# AD9156.net
KiCad netlist of a schematic drawn in Altium Designer
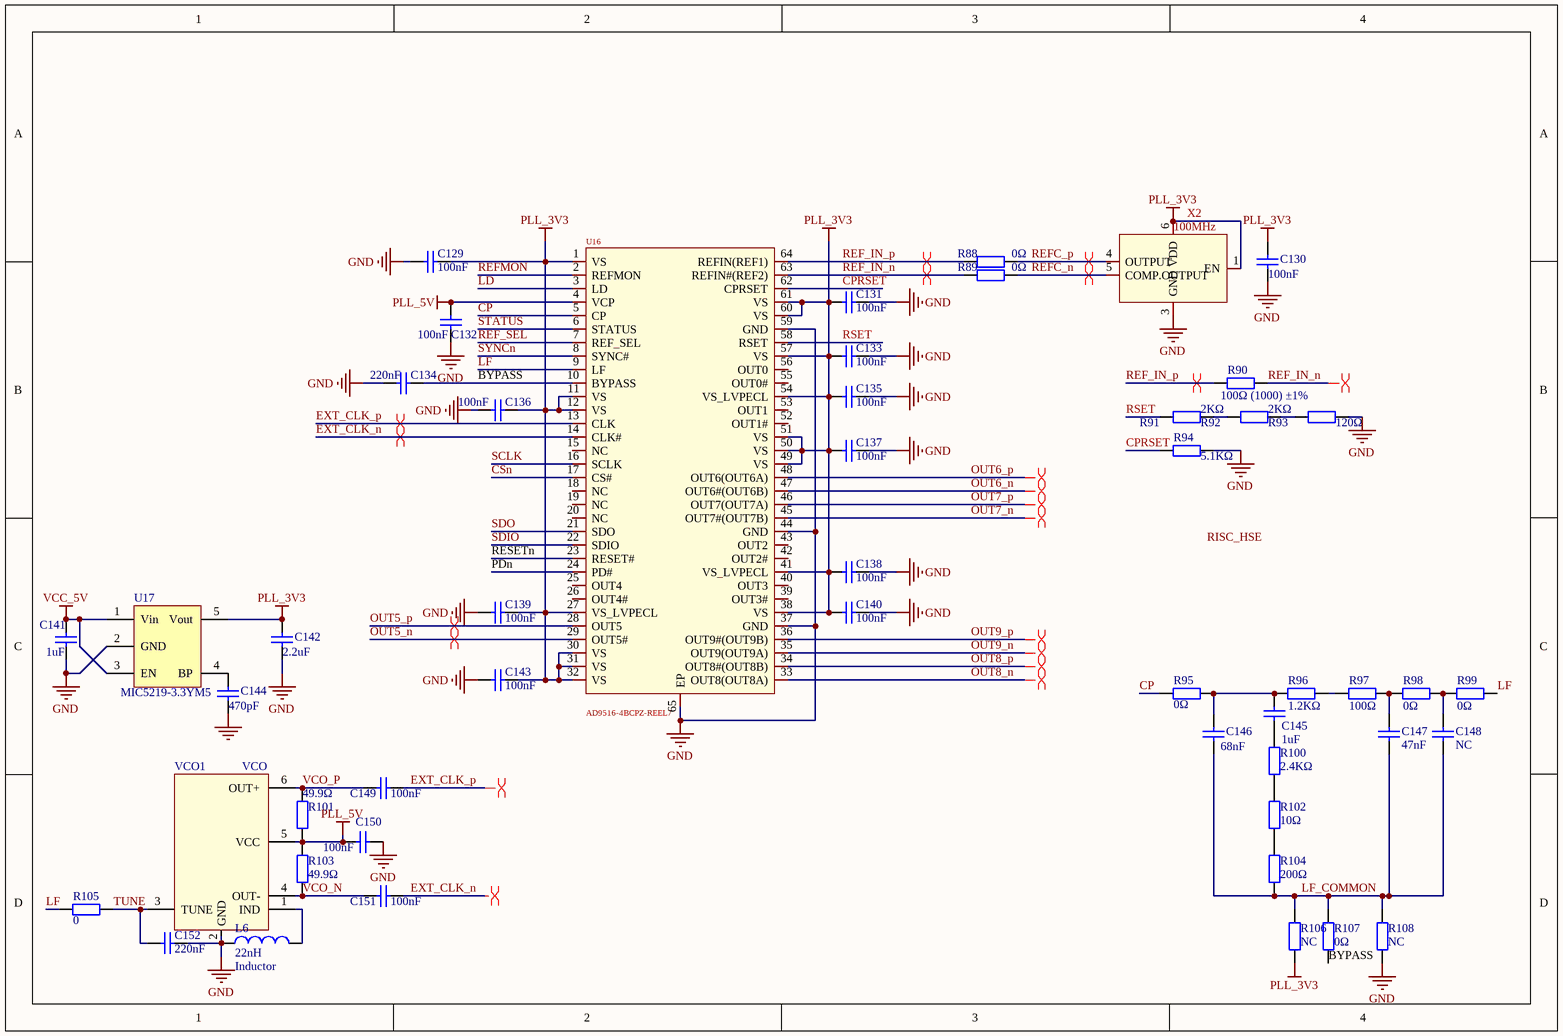
[diagram p0: AD9156.SchDoc]

(export (version "E")
  (design (tool "Eeschema 10.0.6"))
  (components
    (comp (ref "C129")
      (value "100nF")
      (footprint "0201")
      (description "贴片电容")
      (libsource (lib "Miscellaneous Devices LC") (part "0402 100nF (104) 10% 16V"))
    )
    (comp (ref "C130")
      (value "100nF")
      (footprint "0201")
      (description "贴片电容")
      (libsource (lib "Miscellaneous Devices LC") (part "0402 100nF (104) 10% 16V"))
    )
    (comp (ref "C131")
      (value "100nF")
      (footprint "0201")
      (description "贴片电容")
      (libsource (lib "Miscellaneous Devices LC") (part "0402 100nF (104) 10% 16V"))
    )
    (comp (ref "C132")
      (value "100nF")
      (footprint "0201")
      (description "贴片电容")
      (libsource (lib "Miscellaneous Devices LC") (part "0402 100nF (104) 10% 16V"))
    )
    (comp (ref "C133")
      (value "100nF")
      (footprint "0201")
      (description "贴片电容")
      (libsource (lib "Miscellaneous Devices LC") (part "0402 100nF (104) 10% 16V"))
    )
    (comp (ref "C134")
      (value "220nF")
      (footprint "0805_C")
      (description "贴片电容")
      (libsource (lib "Miscellaneous Devices LC") (part "0402 220nF (224) 10% 16V"))
    )
    (comp (ref "C135")
      (value "100nF")
      (footprint "0201")
      (description "贴片电容")
      (libsource (lib "Miscellaneous Devices LC") (part "0402 100nF (104) 10% 16V"))
    )
    (comp (ref "C136")
      (value "100nF")
      (footprint "0201")
      (description "贴片电容")
      (libsource (lib "Miscellaneous Devices LC") (part "0402 100nF (104) 10% 16V"))
    )
    (comp (ref "C137")
      (value "100nF")
      (footprint "0201")
      (description "贴片电容")
      (libsource (lib "Miscellaneous Devices LC") (part "0402 100nF (104) 10% 16V"))
    )
    (comp (ref "C138")
      (value "100nF")
      (footprint "0201")
      (description "贴片电容")
      (libsource (lib "Miscellaneous Devices LC") (part "0402 100nF (104) 10% 16V"))
    )
    (comp (ref "C139")
      (value "100nF")
      (footprint "0201")
      (description "贴片电容")
      (libsource (lib "Miscellaneous Devices LC") (part "0402 100nF (104) 10% 16V"))
    )
    (comp (ref "C140")
      (value "100nF")
      (footprint "0201")
      (description "贴片电容")
      (libsource (lib "Miscellaneous Devices LC") (part "0402 100nF (104) 10% 16V"))
    )
    (comp (ref "C141")
      (value "1uF")
      (footprint "0805_C")
      (description "贴片电容")
      (libsource (lib "Miscellaneous Devices LC") (part "0805 1uF (105) 10% 50V"))
    )
    (comp (ref "C142")
      (value "2.2uF")
      (footprint "0805_C")
      (description "贴片电容")
      (libsource (lib "Miscellaneous Devices LC") (part "0805 1uF (105) 10% 50V"))
    )
    (comp (ref "C143")
      (value "100nF")
      (footprint "0201")
      (description "贴片电容")
      (libsource (lib "Miscellaneous Devices LC") (part "0402 100nF (104) 10% 16V"))
    )
    (comp (ref "C144")
      (value "470pF")
      (footprint "0805_C")
      (description "贴片电容")
      (libsource (lib "Miscellaneous Devices LC") (part "0805 1uF (105) 10% 50V"))
    )
    (comp (ref "C145")
      (value "1uF")
      (footprint "0805_C")
      (description "贴片电容")
      (libsource (lib "Miscellaneous Devices LC") (part "0805 47nF (473) 10% 50V"))
    )
    (comp (ref "C146")
      (value "68nF")
      (footprint "0805_C")
      (description "贴片电容")
      (libsource (lib "Miscellaneous Devices LC") (part "0603 68nF (683) 10% 50V"))
    )
    (comp (ref "C147")
      (value "47nF")
      (footprint "0805_C")
      (description "贴片电容")
      (libsource (lib "Miscellaneous Devices LC") (part "0805 47nF (473) 10% 50V"))
    )
    (comp (ref "C148")
      (value "NC")
      (footprint "0805_C")
      (description "贴片电容")
      (libsource (lib "Miscellaneous Devices LC") (part "0805 47nF (473) 10% 50V"))
    )
    (comp (ref "C149")
      (value "100nF")
      (footprint "0805_C")
      (description "贴片电容")
      (libsource (lib "Miscellaneous Devices LC") (part "0805 100nF(104) 10% 50V"))
    )
    (comp (ref "C150")
      (value "100nF")
      (footprint "0805_C")
      (description "贴片电容")
      (libsource (lib "Miscellaneous Devices LC") (part "0805 100nF(104) 10% 50V"))
    )
    (comp (ref "C151")
      (value "100nF")
      (footprint "0805_C")
      (description "贴片电容")
      (libsource (lib "Miscellaneous Devices LC") (part "0805 100nF(104) 10% 50V"))
    )
    (comp (ref "C152")
      (value "220nF")
      (footprint "0805_C")
      (description "贴片电容")
      (libsource (lib "Miscellaneous Devices LC") (part "0805 100nF(104) 10% 50V"))
    )
    (comp (ref "L6")
      (value "Inductor")
      (footprint "0805_L")
      (fields (field (name "ALTIUM_VALUE") "22nH") (field (name "PUBLISHER") "Altium Limited"))
      (libsource (lib "Miscellaneous Devices") (part "Inductor"))
    )
    (comp (ref "R88")
      (value "0Ω")
      (footprint "0805_R")
      (description "贴片电阻")
      (libsource (lib "Miscellaneous Devices LC") (part "0402 0Ω (0R0) 1%"))
    )
    (comp (ref "R89")
      (value "0Ω")
      (footprint "0805_R")
      (description "贴片电阻")
      (libsource (lib "Miscellaneous Devices LC") (part "0402 0Ω (0R0) 1%"))
    )
    (comp (ref "R90")
      (value "100Ω (1000) ±1%")
      (footprint "0805_R")
      (description "贴片电阻")
      (libsource (lib "Miscellaneous Devices LC") (part "0402 100Ω (1000) 1%"))
    )
    (comp (ref "R91")
      (value "2KΩ")
      (footprint "0805_R")
      (description "贴片电阻")
      (libsource (lib "Miscellaneous Devices LC") (part "0402 2KΩ (2001) 1%"))
    )
    (comp (ref "R92")
      (value "2KΩ")
      (footprint "0805_R")
      (description "贴片电阻")
      (libsource (lib "Miscellaneous Devices LC") (part "0402 2KΩ (2001) 1%"))
    )
    (comp (ref "R93")
      (value "120Ω")
      (footprint "0805_R")
      (description "贴片电阻")
      (libsource (lib "Miscellaneous Devices LC") (part "0402 120KΩ (1203) 1%"))
    )
    (comp (ref "R94")
      (value "5.1KΩ")
      (footprint "0805_R")
      (description "贴片电阻")
      (libsource (lib "Miscellaneous Devices LC") (part "0402 5.1KΩ (5101) 1%"))
    )
    (comp (ref "R95")
      (value "0Ω")
      (footprint "0805_R")
      (description "贴片电阻")
      (libsource (lib "") (part "0805 0Ω (0R0) 1%_1"))
    )
    (comp (ref "R96")
      (value "1.2KΩ")
      (footprint "0805_R")
      (description "贴片电阻")
      (libsource (lib "") (part "0805 0Ω (0R0) 1%_1"))
    )
    (comp (ref "R97")
      (value "100Ω")
      (footprint "0805_R")
      (description "贴片电阻")
      (libsource (lib "") (part "0805 0Ω (0R0) 1%_1"))
    )
    (comp (ref "R98")
      (value "0Ω")
      (footprint "0805_R")
      (description "贴片电阻")
      (libsource (lib "") (part "0805 0Ω (0R0) 1%_1"))
    )
    (comp (ref "R99")
      (value "0Ω")
      (footprint "0805_R")
      (description "贴片电阻")
      (libsource (lib "") (part "0805 0Ω (0R0) 1%_1"))
    )
    (comp (ref "R100")
      (value "2.4KΩ")
      (footprint "0805_R")
      (description "贴片电阻")
      (libsource (lib "Miscellaneous Devices LC") (part "0805 0Ω (0R0) 1%"))
    )
    (comp (ref "R101")
      (value "49.9Ω")
      (footprint "0805_R")
      (description "贴片电阻")
      (libsource (lib "Miscellaneous Devices LC") (part "0805 49.9Ω (49R9) 1%"))
    )
    (comp (ref "R102")
      (value "10Ω")
      (footprint "0805_R")
      (description "贴片电阻")
      (libsource (lib "Miscellaneous Devices LC") (part "0805 0Ω (0R0) 1%"))
    )
    (comp (ref "R103")
      (value "49.9Ω")
      (footprint "0805_R")
      (description "贴片电阻")
      (libsource (lib "Miscellaneous Devices LC") (part "0805 49.9Ω (49R9) 1%"))
    )
    (comp (ref "R104")
      (value "200Ω")
      (footprint "0805_R")
      (description "贴片电阻")
      (libsource (lib "Miscellaneous Devices LC") (part "0805 0Ω (0R0) 1%"))
    )
    (comp (ref "R105")
      (value "0")
      (footprint "0805_R")
      (description "贴片电阻")
      (libsource (lib "") (part "0805 49.9Ω (49R9) 1%_1"))
    )
    (comp (ref "R106")
      (value "NC")
      (footprint "0805_R")
      (description "贴片电阻")
      (libsource (lib "Miscellaneous Devices LC") (part "0805 0Ω (0R0) 1%"))
    )
    (comp (ref "R107")
      (value "0Ω")
      (footprint "0805_R")
      (description "贴片电阻")
      (libsource (lib "Miscellaneous Devices LC") (part "0805 0Ω (0R0) 1%"))
    )
    (comp (ref "R108")
      (value "NC")
      (footprint "0805_R")
      (description "贴片电阻")
      (libsource (lib "Miscellaneous Devices LC") (part "0805 0Ω (0R0) 1%"))
    )
    (comp (ref "U16")
      (value "AD9516-4BCPZ-REEL7")
      (footprint "LFCSP-64_L9.0-W8.8-P0.50-TL-EP6.2")
      (description "时钟分配芯片")
      (fields (field (name "MANUFACTURER") "ADI(亚德诺)"))
      (libsource (lib "yy_tech") (part "AD9516-4BCPZ-REEL7"))
    )
    (comp (ref "U17")
      (value "MIC5219-3.3YM5")
      (footprint "SOT-23-5")
      (description "3.3v低压差稳压芯片")
      (libsource (lib "五向开关") (part "RT9193-33"))
    )
    (comp (ref "VCO1")
      (value "VCO")
      (footprint "SOT-23-6_L2.9-W1.6-P0.95-LS2.8-BL")
      (description "300MHz~500MHz VCO")
      (libsource (lib "五向开关") (part "MAX2608"))
    )
    (comp (ref "X2")
      (value "100MHz")
      (footprint "OSC-SMD_6P-L3.2-W2.5-BL_SG3225EAN")
      (description "3225有源差分晶体")
      (fields
        (field (name "MANUFACTURER") "SCTF(星通时频)")
        (field (name "MANUFACTURER PART") "SX3DF100.000B20F30PNN")
      )
      (libsource (lib "五向开关") (part "SX3DF100.000B20F30PNN"))
    )
  )
  (nets
    (net (code "1") (name "/BYPASS") (class "Default")
      (node (ref "C134") (pin "2") (pinfunction "2_2") (pintype "passive"))
      (node (ref "R107") (pin "1") (pinfunction "1_1") (pintype "passive"))
      (node (ref "U16") (pin "10") (pinfunction "BYPASS_10") (pintype "passive"))
    )
    (net (code "2") (name "/CP") (class "Default")
      (node (ref "R95") (pin "1") (pinfunction "1_1") (pintype "passive"))
      (node (ref "U16") (pin "5") (pinfunction "CP_5") (pintype "passive"))
    )
    (net (code "3") (name "/CPRSET") (class "Default")
      (node (ref "R94") (pin "1") (pinfunction "1_1") (pintype "passive"))
      (node (ref "U16") (pin "62") (pinfunction "CPRSET_62") (pintype "passive"))
    )
    (net (code "4") (name "/CSn") (class "Default")
      (node (ref "U16") (pin "17") (pinfunction "CS#_17") (pintype "passive"))
    )
    (net (code "5") (name "/EXT_CLK_n") (class "Default")
      (node (ref "C151") (pin "1") (pinfunction "1_1") (pintype "passive"))
      (node (ref "U16") (pin "14") (pinfunction "CLK#_14") (pintype "passive"))
    )
    (net (code "6") (name "/EXT_CLK_p") (class "Default")
      (node (ref "C149") (pin "1") (pinfunction "1_1") (pintype "passive"))
      (node (ref "U16") (pin "13") (pinfunction "CLK_13") (pintype "passive"))
    )
    (net (code "7") (name "/LD") (class "Default")
      (node (ref "U16") (pin "3") (pinfunction "LD_3") (pintype "passive"))
    )
    (net (code "8") (name "/LF") (class "Default")
      (node (ref "R105") (pin "2") (pinfunction "2_2") (pintype "passive"))
      (node (ref "R99") (pin "2") (pinfunction "2_2") (pintype "passive"))
      (node (ref "U16") (pin "9") (pinfunction "LF_9") (pintype "passive"))
    )
    (net (code "9") (name "/LF_COMMON") (class "Default")
      (node (ref "C146") (pin "1") (pinfunction "1_1") (pintype "passive"))
      (node (ref "C147") (pin "1") (pinfunction "1_1") (pintype "passive"))
      (node (ref "C148") (pin "1") (pinfunction "1_1") (pintype "passive"))
      (node (ref "R104") (pin "1") (pinfunction "1_1") (pintype "passive"))
      (node (ref "R106") (pin "2") (pinfunction "2_2") (pintype "passive"))
      (node (ref "R107") (pin "2") (pinfunction "2_2") (pintype "passive"))
      (node (ref "R108") (pin "2") (pinfunction "2_2") (pintype "passive"))
    )
    (net (code "10") (name "/OUT5_n") (class "Default")
      (node (ref "U16") (pin "29") (pinfunction "OUT5#_29") (pintype "passive"))
    )
    (net (code "11") (name "/OUT5_p") (class "Default")
      (node (ref "U16") (pin "28") (pinfunction "OUT5_28") (pintype "passive"))
    )
    (net (code "12") (name "/OUT6_n") (class "Default")
      (node (ref "U16") (pin "47") (pinfunction "OUT6#(OUT6B)_47") (pintype "passive"))
    )
    (net (code "13") (name "/OUT6_p") (class "Default")
      (node (ref "U16") (pin "48") (pinfunction "OUT6(OUT6A)_48") (pintype "passive"))
    )
    (net (code "14") (name "/OUT7_n") (class "Default")
      (node (ref "U16") (pin "45") (pinfunction "OUT7#(OUT7B)_45") (pintype "passive"))
    )
    (net (code "15") (name "/OUT7_p") (class "Default")
      (node (ref "U16") (pin "46") (pinfunction "OUT7(OUT7A)_46") (pintype "passive"))
    )
    (net (code "16") (name "/OUT8_n") (class "Default")
      (node (ref "U16") (pin "33") (pinfunction "OUT8(OUT8A)_33") (pintype "passive"))
    )
    (net (code "17") (name "/OUT8_p") (class "Default")
      (node (ref "U16") (pin "34") (pinfunction "OUT8#(OUT8B)_34") (pintype "passive"))
    )
    (net (code "18") (name "/OUT9_n") (class "Default")
      (node (ref "U16") (pin "35") (pinfunction "OUT9(OUT9A)_35") (pintype "passive"))
    )
    (net (code "19") (name "/OUT9_p") (class "Default")
      (node (ref "U16") (pin "36") (pinfunction "OUT9#(OUT9B)_36") (pintype "passive"))
    )
    (net (code "20") (name "/PDn") (class "Default")
      (node (ref "U16") (pin "24") (pinfunction "PD#_24") (pintype "passive"))
    )
    (net (code "21") (name "/REFC_n") (class "Default")
      (node (ref "R89") (pin "2") (pinfunction "2_2") (pintype "passive"))
      (node (ref "X2") (pin "5") (pinfunction "COMP.OUTPUT_5") (pintype "passive"))
    )
    (net (code "22") (name "/REFC_p") (class "Default")
      (node (ref "R88") (pin "2") (pinfunction "2_2") (pintype "passive"))
      (node (ref "X2") (pin "4") (pinfunction "OUTPUT_4") (pintype "passive"))
    )
    (net (code "23") (name "/REFMON") (class "Default")
      (node (ref "U16") (pin "2") (pinfunction "REFMON_2") (pintype "passive"))
    )
    (net (code "24") (name "/REF_IN_n") (class "Default")
      (node (ref "R89") (pin "1") (pinfunction "1_1") (pintype "passive"))
      (node (ref "R90") (pin "1") (pinfunction "1_1") (pintype "passive"))
      (node (ref "U16") (pin "63") (pinfunction "REFIN#(REF2)_63") (pintype "passive"))
    )
    (net (code "25") (name "/REF_IN_p") (class "Default")
      (node (ref "R88") (pin "1") (pinfunction "1_1") (pintype "passive"))
      (node (ref "R90") (pin "2") (pinfunction "2_2") (pintype "passive"))
      (node (ref "U16") (pin "64") (pinfunction "REFIN(REF1)_64") (pintype "passive"))
    )
    (net (code "26") (name "/REF_SEL") (class "Default")
      (node (ref "U16") (pin "7") (pinfunction "REF_SEL_7") (pintype "passive"))
    )
    (net (code "27") (name "/RESETn") (class "Default")
      (node (ref "U16") (pin "23") (pinfunction "RESET#_23") (pintype "passive"))
    )
    (net (code "29") (name "/RSET") (class "Default")
      (node (ref "R91") (pin "1") (pinfunction "1_1") (pintype "passive"))
      (node (ref "U16") (pin "58") (pinfunction "RSET_58") (pintype "passive"))
    )
    (net (code "30") (name "/SCLK") (class "Default")
      (node (ref "U16") (pin "16") (pinfunction "SCLK_16") (pintype "passive"))
    )
    (net (code "31") (name "/SDIO") (class "Default")
      (node (ref "U16") (pin "22") (pinfunction "SDIO_22") (pintype "passive"))
    )
    (net (code "32") (name "/SDO") (class "Default")
      (node (ref "U16") (pin "21") (pinfunction "SDO_21") (pintype "passive"))
    )
    (net (code "33") (name "/STATUS") (class "Default")
      (node (ref "U16") (pin "6") (pinfunction "STATUS_6") (pintype "passive"))
    )
    (net (code "34") (name "/SYNCn") (class "Default")
      (node (ref "U16") (pin "8") (pinfunction "SYNC#_8") (pintype "passive"))
    )
    (net (code "35") (name "/TUNE") (class "Default")
      (node (ref "C152") (pin "2") (pinfunction "2_2") (pintype "passive"))
      (node (ref "R105") (pin "1") (pinfunction "1_1") (pintype "passive"))
      (node (ref "VCO1") (pin "3") (pinfunction "TUNE_3") (pintype "passive"))
    )
    (net (code "36") (name "/VCO_N") (class "Default")
      (node (ref "C151") (pin "2") (pinfunction "2_2") (pintype "passive"))
      (node (ref "R103") (pin "1") (pinfunction "1_1") (pintype "passive"))
      (node (ref "VCO1") (pin "4") (pinfunction "OUT-_4") (pintype "passive"))
    )
    (net (code "37") (name "/VCO_P") (class "Default")
      (node (ref "C149") (pin "2") (pinfunction "2_2") (pintype "passive"))
      (node (ref "R101") (pin "2") (pinfunction "2_2") (pintype "passive"))
      (node (ref "VCO1") (pin "6") (pinfunction "OUT+_6") (pintype "passive"))
    )
    (net (code "38") (name "GND") (class "Default")
      (node (ref "C129") (pin "1") (pinfunction "1_1") (pintype "passive"))
      (node (ref "C130") (pin "1") (pinfunction "1_1") (pintype "passive"))
      (node (ref "C131") (pin "2") (pinfunction "2_2") (pintype "passive"))
      (node (ref "C132") (pin "1") (pinfunction "1_1") (pintype "passive"))
      (node (ref "C133") (pin "2") (pinfunction "2_2") (pintype "passive"))
      (node (ref "C134") (pin "1") (pinfunction "1_1") (pintype "passive"))
      (node (ref "C135") (pin "1") (pinfunction "1_1") (pintype "passive"))
      (node (ref "C136") (pin "1") (pinfunction "1_1") (pintype "passive"))
      (node (ref "C137") (pin "2") (pinfunction "2_2") (pintype "passive"))
      (node (ref "C138") (pin "1") (pinfunction "1_1") (pintype "passive"))
      (node (ref "C139") (pin "1") (pinfunction "1_1") (pintype "passive"))
      (node (ref "C140") (pin "2") (pinfunction "2_2") (pintype "passive"))
      (node (ref "C141") (pin "1") (pinfunction "1_1") (pintype "passive"))
      (node (ref "C142") (pin "1") (pinfunction "1_1") (pintype "passive"))
      (node (ref "C143") (pin "1") (pinfunction "1_1") (pintype "passive"))
      (node (ref "C144") (pin "1") (pinfunction "1_1") (pintype "passive"))
      (node (ref "C150") (pin "1") (pinfunction "1_1") (pintype "passive"))
      (node (ref "C152") (pin "1") (pinfunction "1_1") (pintype "passive"))
      (node (ref "L6") (pin "1") (pinfunction "1_1") (pintype "passive"))
      (node (ref "R108") (pin "1") (pinfunction "1_1") (pintype "passive"))
      (node (ref "R93") (pin "2") (pinfunction "2_2") (pintype "passive"))
      (node (ref "R94") (pin "2") (pinfunction "2_2") (pintype "passive"))
      (node (ref "U16") (pin "37") (pinfunction "GND_37") (pintype "passive"))
      (node (ref "U16") (pin "44") (pinfunction "GND_44") (pintype "passive"))
      (node (ref "U16") (pin "59") (pinfunction "GND_59") (pintype "passive"))
      (node (ref "U16") (pin "65") (pinfunction "EP_65") (pintype "passive"))
      (node (ref "U17") (pin "2") (pinfunction "GND_2") (pintype "passive"))
      (node (ref "VCO1") (pin "2") (pinfunction "GND_2") (pintype "passive"))
      (node (ref "X2") (pin "3") (pinfunction "GND_3") (pintype "passive"))
    )
    (net (code "39") (name "Net-(C145-Pad1)") (class "Default")
      (node (ref "C145") (pin "1") (pinfunction "1_1") (pintype "passive"))
      (node (ref "R100") (pin "2") (pinfunction "2_2") (pintype "passive"))
    )
    (net (code "40") (name "Net-(C145-Pad2)") (class "Default")
      (node (ref "C145") (pin "2") (pinfunction "2_2") (pintype "passive"))
      (node (ref "C146") (pin "2") (pinfunction "2_2") (pintype "passive"))
      (node (ref "R95") (pin "2") (pinfunction "2_2") (pintype "passive"))
      (node (ref "R96") (pin "1") (pinfunction "1_1") (pintype "passive"))
    )
    (net (code "41") (name "Net-(C147-Pad2)") (class "Default")
      (node (ref "C147") (pin "2") (pinfunction "2_2") (pintype "passive"))
      (node (ref "R97") (pin "2") (pinfunction "2_2") (pintype "passive"))
      (node (ref "R98") (pin "1") (pinfunction "1_1") (pintype "passive"))
    )
    (net (code "42") (name "Net-(C148-Pad2)") (class "Default")
      (node (ref "C148") (pin "2") (pinfunction "2_2") (pintype "passive"))
      (node (ref "R98") (pin "2") (pinfunction "2_2") (pintype "passive"))
      (node (ref "R99") (pin "1") (pinfunction "1_1") (pintype "passive"))
    )
    (net (code "43") (name "Net-(R91-Pad2)") (class "Default")
      (node (ref "R91") (pin "2") (pinfunction "2_2") (pintype "passive"))
      (node (ref "R92") (pin "1") (pinfunction "1_1") (pintype "passive"))
    )
    (net (code "44") (name "Net-(R92-Pad2)") (class "Default")
      (node (ref "R92") (pin "2") (pinfunction "2_2") (pintype "passive"))
      (node (ref "R93") (pin "1") (pinfunction "1_1") (pintype "passive"))
    )
    (net (code "45") (name "Net-(R96-Pad2)") (class "Default")
      (node (ref "R96") (pin "2") (pinfunction "2_2") (pintype "passive"))
      (node (ref "R97") (pin "1") (pinfunction "1_1") (pintype "passive"))
    )
    (net (code "46") (name "Net-(R100-Pad1)") (class "Default")
      (node (ref "R100") (pin "1") (pinfunction "1_1") (pintype "passive"))
      (node (ref "R102") (pin "2") (pinfunction "2_2") (pintype "passive"))
    )
    (net (code "47") (name "Net-(R102-Pad1)") (class "Default")
      (node (ref "R102") (pin "1") (pinfunction "1_1") (pintype "passive"))
      (node (ref "R104") (pin "2") (pinfunction "2_2") (pintype "passive"))
    )
    (net (code "48") (name "Net-(U17-BP)") (class "Default")
      (node (ref "C144") (pin "2") (pinfunction "2_2") (pintype "passive"))
      (node (ref "U17") (pin "4") (pinfunction "BP_4") (pintype "passive"))
    )
    (net (code "49") (name "Net-(VCO1-IND)") (class "Default")
      (node (ref "L6") (pin "2") (pinfunction "2_2") (pintype "passive"))
      (node (ref "VCO1") (pin "1") (pinfunction "IND_1") (pintype "passive"))
    )
    (net (code "50") (name "PLL_3V3") (class "Default")
      (node (ref "C129") (pin "2") (pinfunction "2_2") (pintype "passive"))
      (node (ref "C130") (pin "2") (pinfunction "2_2") (pintype "passive"))
      (node (ref "C131") (pin "1") (pinfunction "1_1") (pintype "passive"))
      (node (ref "C133") (pin "1") (pinfunction "1_1") (pintype "passive"))
      (node (ref "C135") (pin "2") (pinfunction "2_2") (pintype "passive"))
      (node (ref "C136") (pin "2") (pinfunction "2_2") (pintype "passive"))
      (node (ref "C137") (pin "1") (pinfunction "1_1") (pintype "passive"))
      (node (ref "C138") (pin "2") (pinfunction "2_2") (pintype "passive"))
      (node (ref "C139") (pin "2") (pinfunction "2_2") (pintype "passive"))
      (node (ref "C140") (pin "1") (pinfunction "1_1") (pintype "passive"))
      (node (ref "C142") (pin "2") (pinfunction "2_2") (pintype "passive"))
      (node (ref "C143") (pin "2") (pinfunction "2_2") (pintype "passive"))
      (node (ref "R106") (pin "1") (pinfunction "1_1") (pintype "passive"))
      (node (ref "U16") (pin "1") (pinfunction "VS_1") (pintype "passive"))
      (node (ref "U16") (pin "11") (pinfunction "VS_11") (pintype "passive"))
      (node (ref "U16") (pin "12") (pinfunction "VS_12") (pintype "passive"))
      (node (ref "U16") (pin "27") (pinfunction "VS_LVPECL_27") (pintype "passive"))
      (node (ref "U16") (pin "30") (pinfunction "VS_30") (pintype "passive"))
      (node (ref "U16") (pin "31") (pinfunction "VS_31") (pintype "passive"))
      (node (ref "U16") (pin "32") (pinfunction "VS_32") (pintype "passive"))
      (node (ref "U16") (pin "38") (pinfunction "VS_38") (pintype "passive"))
      (node (ref "U16") (pin "41") (pinfunction "VS_LVPECL_41") (pintype "passive"))
      (node (ref "U16") (pin "49") (pinfunction "VS_49") (pintype "passive"))
      (node (ref "U16") (pin "50") (pinfunction "VS_50") (pintype "passive"))
      (node (ref "U16") (pin "51") (pinfunction "VS_51") (pintype "passive"))
      (node (ref "U16") (pin "54") (pinfunction "VS_LVPECL_54") (pintype "passive"))
      (node (ref "U16") (pin "57") (pinfunction "VS_57") (pintype "passive"))
      (node (ref "U16") (pin "60") (pinfunction "VS_60") (pintype "passive"))
      (node (ref "U16") (pin "61") (pinfunction "VS_61") (pintype "passive"))
      (node (ref "U17") (pin "5") (pinfunction "Vout_5") (pintype "passive"))
      (node (ref "X2") (pin "1") (pinfunction "EN_1") (pintype "passive"))
      (node (ref "X2") (pin "6") (pinfunction "VDD_6") (pintype "passive"))
    )
    (net (code "51") (name "PLL_5V") (class "Default")
      (node (ref "C132") (pin "2") (pinfunction "2_2") (pintype "passive"))
      (node (ref "C150") (pin "2") (pinfunction "2_2") (pintype "passive"))
      (node (ref "R101") (pin "1") (pinfunction "1_1") (pintype "passive"))
      (node (ref "R103") (pin "2") (pinfunction "2_2") (pintype "passive"))
      (node (ref "U16") (pin "4") (pinfunction "VCP_4") (pintype "passive"))
      (node (ref "VCO1") (pin "5") (pinfunction "VCC_5") (pintype "passive"))
    )
    (net (code "52") (name "VCC_5V") (class "Default")
      (node (ref "C141") (pin "2") (pinfunction "2_2") (pintype "passive"))
      (node (ref "U17") (pin "1") (pinfunction "Vin_1") (pintype "passive"))
      (node (ref "U17") (pin "3") (pinfunction "EN_3") (pintype "passive"))
    )
    (net (code "53") (name "unconnected-(U16-NC-Pad15)") (class "Default")
      (node (ref "U16") (pin "15") (pinfunction "NC_15") (pintype "passive"))
    )
    (net (code "54") (name "unconnected-(U16-NC-Pad18)") (class "Default")
      (node (ref "U16") (pin "18") (pinfunction "NC_18") (pintype "passive"))
    )
    (net (code "55") (name "unconnected-(U16-NC-Pad19)") (class "Default")
      (node (ref "U16") (pin "19") (pinfunction "NC_19") (pintype "passive"))
    )
    (net (code "56") (name "unconnected-(U16-NC-Pad20)") (class "Default")
      (node (ref "U16") (pin "20") (pinfunction "NC_20") (pintype "passive"))
    )
    (net (code "57") (name "unconnected-(U16-OUT0#-Pad55)") (class "Default")
      (node (ref "U16") (pin "55") (pinfunction "OUT0#_55") (pintype "passive"))
    )
    (net (code "58") (name "unconnected-(U16-OUT0-Pad56)") (class "Default")
      (node (ref "U16") (pin "56") (pinfunction "OUT0_56") (pintype "passive"))
    )
    (net (code "59") (name "unconnected-(U16-OUT1#-Pad52)") (class "Default")
      (node (ref "U16") (pin "52") (pinfunction "OUT1#_52") (pintype "passive"))
    )
    (net (code "60") (name "unconnected-(U16-OUT1-Pad53)") (class "Default")
      (node (ref "U16") (pin "53") (pinfunction "OUT1_53") (pintype "passive"))
    )
    (net (code "61") (name "unconnected-(U16-OUT2#-Pad42)") (class "Default")
      (node (ref "U16") (pin "42") (pinfunction "OUT2#_42") (pintype "passive"))
    )
    (net (code "62") (name "unconnected-(U16-OUT2-Pad43)") (class "Default")
      (node (ref "U16") (pin "43") (pinfunction "OUT2_43") (pintype "passive"))
    )
    (net (code "63") (name "unconnected-(U16-OUT3#-Pad39)") (class "Default")
      (node (ref "U16") (pin "39") (pinfunction "OUT3#_39") (pintype "passive"))
    )
    (net (code "64") (name "unconnected-(U16-OUT3-Pad40)") (class "Default")
      (node (ref "U16") (pin "40") (pinfunction "OUT3_40") (pintype "passive"))
    )
    (net (code "65") (name "unconnected-(U16-OUT4#-Pad26)") (class "Default")
      (node (ref "U16") (pin "26") (pinfunction "OUT4#_26") (pintype "passive"))
    )
    (net (code "66") (name "unconnected-(U16-OUT4-Pad25)") (class "Default")
      (node (ref "U16") (pin "25") (pinfunction "OUT4_25") (pintype "passive"))
    )
  )
)
